# power_board.net
KiCad netlist of a schematic drawn in EAGLE
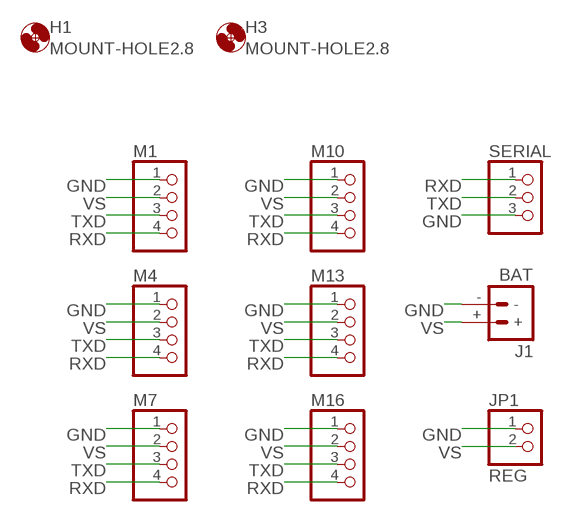
[diagram p0: schematic, sheet 1]

(export (version "E")
  (design (tool "Eeschema 10.0.6"))
  (components
    (comp (ref "H1")
      (value "MOUNT-HOLE2.8")
      (footprint "eagle-import:2,8")
      (libsource (lib "eagle-import") (part "MOUNT-HOLE2.8"))
    )
    (comp (ref "H3")
      (value "MOUNT-HOLE2.8")
      (footprint "eagle-import:2,8")
      (libsource (lib "eagle-import") (part "MOUNT-HOLE2.8"))
    )
    (comp (ref "J1")
      (value "BAT")
      (footprint "eagle-import:DEANS")
      (libsource (lib "eagle-import") (part "BATTERY_CONN_DEANS"))
    )
    (comp (ref "JP1")
      (value "REG")
      (footprint "eagle-import:1X02")
      (libsource (lib "eagle-import") (part "PINHD-1X2"))
    )
    (comp (ref "M1")
      (value "PINHD-1X4")
      (footprint "eagle-import:1X04")
      (libsource (lib "eagle-import") (part "PINHD-1X4"))
    )
    (comp (ref "M4")
      (value "PINHD-1X4")
      (footprint "eagle-import:1X04")
      (libsource (lib "eagle-import") (part "PINHD-1X4"))
    )
    (comp (ref "M7")
      (value "PINHD-1X4")
      (footprint "eagle-import:1X04")
      (libsource (lib "eagle-import") (part "PINHD-1X4"))
    )
    (comp (ref "M10")
      (value "PINHD-1X4")
      (footprint "eagle-import:1X04")
      (libsource (lib "eagle-import") (part "PINHD-1X4"))
    )
    (comp (ref "M13")
      (value "PINHD-1X4")
      (footprint "eagle-import:1X04")
      (libsource (lib "eagle-import") (part "PINHD-1X4"))
    )
    (comp (ref "M16")
      (value "PINHD-1X4")
      (footprint "eagle-import:1X04")
      (libsource (lib "eagle-import") (part "PINHD-1X4"))
    )
    (comp (ref "SERIAL")
      (value "PINHD-1X3")
      (footprint "eagle-import:1X03")
      (libsource (lib "eagle-import") (part "PINHD-1X3"))
    )
  )
  (nets
    (net (code "1") (name "/GND") (class "Default")
      (node (ref "J1") (pin "-") (pinfunction "-_-") (pintype "passive"))
      (node (ref "JP1") (pin "1") (pinfunction "1_1") (pintype "passive"))
      (node (ref "M1") (pin "1") (pinfunction "1_1") (pintype "passive"))
      (node (ref "M10") (pin "1") (pinfunction "1_1") (pintype "passive"))
      (node (ref "M13") (pin "1") (pinfunction "1_1") (pintype "passive"))
      (node (ref "M16") (pin "1") (pinfunction "1_1") (pintype "passive"))
      (node (ref "M4") (pin "1") (pinfunction "1_1") (pintype "passive"))
      (node (ref "M7") (pin "1") (pinfunction "1_1") (pintype "passive"))
      (node (ref "SERIAL") (pin "3") (pinfunction "3_3") (pintype "passive"))
    )
    (net (code "2") (name "/RXD") (class "Default")
      (node (ref "M1") (pin "4") (pinfunction "4_4") (pintype "passive"))
      (node (ref "M10") (pin "4") (pinfunction "4_4") (pintype "passive"))
      (node (ref "M13") (pin "4") (pinfunction "4_4") (pintype "passive"))
      (node (ref "M16") (pin "4") (pinfunction "4_4") (pintype "passive"))
      (node (ref "M4") (pin "4") (pinfunction "4_4") (pintype "passive"))
      (node (ref "M7") (pin "4") (pinfunction "4_4") (pintype "passive"))
      (node (ref "SERIAL") (pin "1") (pinfunction "1_1") (pintype "passive"))
    )
    (net (code "3") (name "/TXD") (class "Default")
      (node (ref "M1") (pin "3") (pinfunction "3_3") (pintype "passive"))
      (node (ref "M10") (pin "3") (pinfunction "3_3") (pintype "passive"))
      (node (ref "M13") (pin "3") (pinfunction "3_3") (pintype "passive"))
      (node (ref "M16") (pin "3") (pinfunction "3_3") (pintype "passive"))
      (node (ref "M4") (pin "3") (pinfunction "3_3") (pintype "passive"))
      (node (ref "M7") (pin "3") (pinfunction "3_3") (pintype "passive"))
      (node (ref "SERIAL") (pin "2") (pinfunction "2_2") (pintype "passive"))
    )
    (net (code "4") (name "/VS") (class "Default")
      (node (ref "J1") (pin "+") (pinfunction "+_+") (pintype "passive"))
      (node (ref "JP1") (pin "2") (pinfunction "2_2") (pintype "passive"))
      (node (ref "M1") (pin "2") (pinfunction "2_2") (pintype "passive"))
      (node (ref "M10") (pin "2") (pinfunction "2_2") (pintype "passive"))
      (node (ref "M13") (pin "2") (pinfunction "2_2") (pintype "passive"))
      (node (ref "M16") (pin "2") (pinfunction "2_2") (pintype "passive"))
      (node (ref "M4") (pin "2") (pinfunction "2_2") (pintype "passive"))
      (node (ref "M7") (pin "2") (pinfunction "2_2") (pintype "passive"))
    )
  )
)
